# ISO_PWR_UCC12040DVER.net
KiCad netlist of a schematic drawn in Altium Designer
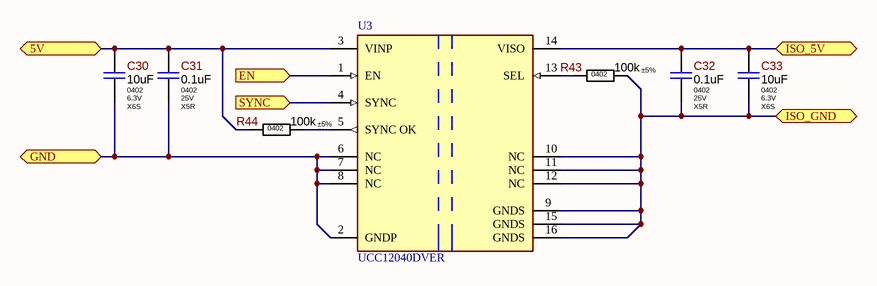
[diagram p0: ISO_PWR_UCC12040DVER.SchDoc]

(export (version "E")
  (design (tool "Eeschema 10.0.6"))
  (components
    (comp (ref "C30")
      (value "10uF")
      (footprint "C_CERAMIC_0402_MED")
      (description "10uF 6.3V X6S ±20% 0402 Ceramic Capacitor RoHS")
      (fields
        (field (name "PACKAGE") "0402")
        (field (name "VOLTAGE") "6.3V")
        (field (name "DIELECTRIC TYPE") "X6S")
        (field (name "PART NUMBER") "GRM155C80J106ME11D")
        (field (name "MANUFACTURER") "Murata Electronics")
      )
      (libsource (lib "EL.XXX.T01") (part "Capacitor-NonPolar"))
    )
    (comp (ref "C31")
      (value "0.1uF")
      (footprint "C_CERAMIC_0402_MED")
      (description "100nF 25V X5R ±10% 0402 Ceramic Capacitor RoHS")
      (fields
        (field (name "PACKAGE") "0402")
        (field (name "VOLTAGE") "25V")
        (field (name "DIELECTRIC TYPE") "X5R")
        (field (name "PART NUMBER") "CL05A104KA5NNNC")
        (field (name "MANUFACTURER") "Samsung Electro-Mechanics")
      )
      (libsource (lib "EL.XXX.T01") (part "Capacitor-NonPolar"))
    )
    (comp (ref "C32")
      (value "0.1uF")
      (footprint "C_CERAMIC_0402_MED")
      (description "100nF 25V X5R ±10% 0402 Ceramic Capacitor RoHS")
      (fields
        (field (name "PACKAGE") "0402")
        (field (name "VOLTAGE") "25V")
        (field (name "DIELECTRIC TYPE") "X5R")
        (field (name "PART NUMBER") "CL05A104KA5NNNC")
        (field (name "MANUFACTURER") "Samsung Electro-Mechanics")
      )
      (libsource (lib "EL.XXX.T01") (part "Capacitor-NonPolar"))
    )
    (comp (ref "C33")
      (value "10uF")
      (footprint "C_CERAMIC_0402_MED")
      (description "10uF 6.3V X6S ±20% 0402 Ceramic Capacitor RoHS")
      (fields
        (field (name "PACKAGE") "0402")
        (field (name "VOLTAGE") "6.3V")
        (field (name "DIELECTRIC TYPE") "X6S")
        (field (name "PART NUMBER") "GRM155C80J106ME11D")
        (field (name "MANUFACTURER") "Murata Electronics")
      )
      (libsource (lib "EL.XXX.T01") (part "Capacitor-NonPolar"))
    )
    (comp (ref "R43")
      (value "100k")
      (footprint "R_ANY_CHIP_0402_HI")
      (description "100 kOhms ±5% 1/16W 0402 Thick Film Resistor")
      (fields
        (field (name "TOLERANCE") "±5%")
        (field (name "PACKAGE") "0402")
        (field (name "PART NUMBER") "RC0402JR-07100KL")
        (field (name "MANUFACTURER") "Yageo")
      )
      (libsource (lib "EL.XXX.T01") (part "Resistor"))
    )
    (comp (ref "R44")
      (value "100k")
      (footprint "R_ANY_CHIP_0402_HI")
      (description "100 kOhms ±5% 1/16W 0402 Thick Film Resistor")
      (fields
        (field (name "TOLERANCE") "±5%")
        (field (name "PACKAGE") "0402")
        (field (name "PART NUMBER") "RC0402JR-07100KL")
        (field (name "MANUFACTURER") "Yageo")
      )
      (libsource (lib "EL.XXX.T01") (part "Resistor"))
    )
    (comp (ref "U3")
      (value "UCC12040DVER")
      (footprint "FP-DVE0016A-MFG")
      (description "DC DC CONVERTER 5V 500mW")
      (libsource (lib "EL.XXX.T01") (part "CMP-04910-000064-1"))
    )
  )
  (nets
    (net (code "1") (name "/5V") (class "Default")
      (node (ref "C30") (pin "1") (pinfunction "1_1") (pintype "passive"))
      (node (ref "C31") (pin "1") (pinfunction "1_1") (pintype "passive"))
      (node (ref "R44") (pin "1") (pintype "passive"))
      (node (ref "U3") (pin "3") (pinfunction "VINP_3") (pintype "power_in"))
    )
    (net (code "2") (name "/EN") (class "Default")
      (node (ref "U3") (pin "1") (pinfunction "EN_1") (pintype "input"))
    )
    (net (code "3") (name "/GND") (class "Default")
      (node (ref "C30") (pin "2") (pinfunction "2_2") (pintype "passive"))
      (node (ref "C31") (pin "2") (pinfunction "2_2") (pintype "passive"))
      (node (ref "U3") (pin "2") (pinfunction "GNDP_2") (pintype "power_in"))
      (node (ref "U3") (pin "6") (pinfunction "NC_6") (pintype "passive"))
      (node (ref "U3") (pin "7") (pinfunction "NC_7") (pintype "passive"))
      (node (ref "U3") (pin "8") (pinfunction "NC_8") (pintype "passive"))
    )
    (net (code "4") (name "/ISO_5V") (class "Default")
      (node (ref "C32") (pin "1") (pinfunction "1_1") (pintype "passive"))
      (node (ref "C33") (pin "1") (pinfunction "1_1") (pintype "passive"))
      (node (ref "U3") (pin "14") (pinfunction "VISO_14") (pintype "power_in"))
    )
    (net (code "5") (name "/ISO_GND") (class "Default")
      (node (ref "C32") (pin "2") (pinfunction "2_2") (pintype "passive"))
      (node (ref "C33") (pin "2") (pinfunction "2_2") (pintype "passive"))
      (node (ref "R43") (pin "2") (pintype "passive"))
      (node (ref "U3") (pin "10") (pinfunction "NC_10") (pintype "passive"))
      (node (ref "U3") (pin "11") (pinfunction "NC_11") (pintype "passive"))
      (node (ref "U3") (pin "12") (pinfunction "NC_12") (pintype "passive"))
      (node (ref "U3") (pin "15") (pinfunction "GNDS_15") (pintype "power_in"))
      (node (ref "U3") (pin "16") (pinfunction "GNDS_16") (pintype "power_in"))
      (node (ref "U3") (pin "9") (pinfunction "GNDS_9") (pintype "power_in"))
    )
    (net (code "6") (name "/SYNC") (class "Default")
      (node (ref "U3") (pin "4") (pinfunction "SYNC_4") (pintype "input"))
    )
    (net (code "7") (name "Net-(U3-SEL)") (class "Default")
      (node (ref "R43") (pin "1") (pintype "passive"))
      (node (ref "U3") (pin "13") (pinfunction "SEL_13") (pintype "input"))
    )
    (net (code "8") (name "Net-(U3-SYNC_OK)") (class "Default")
      (node (ref "R44") (pin "2") (pintype "passive"))
      (node (ref "U3") (pin "5") (pinfunction "SYNC_OK_5") (pintype "output"))
    )
  )
)
